# LNA.net
KiCad netlist of a schematic drawn in Altium Designer
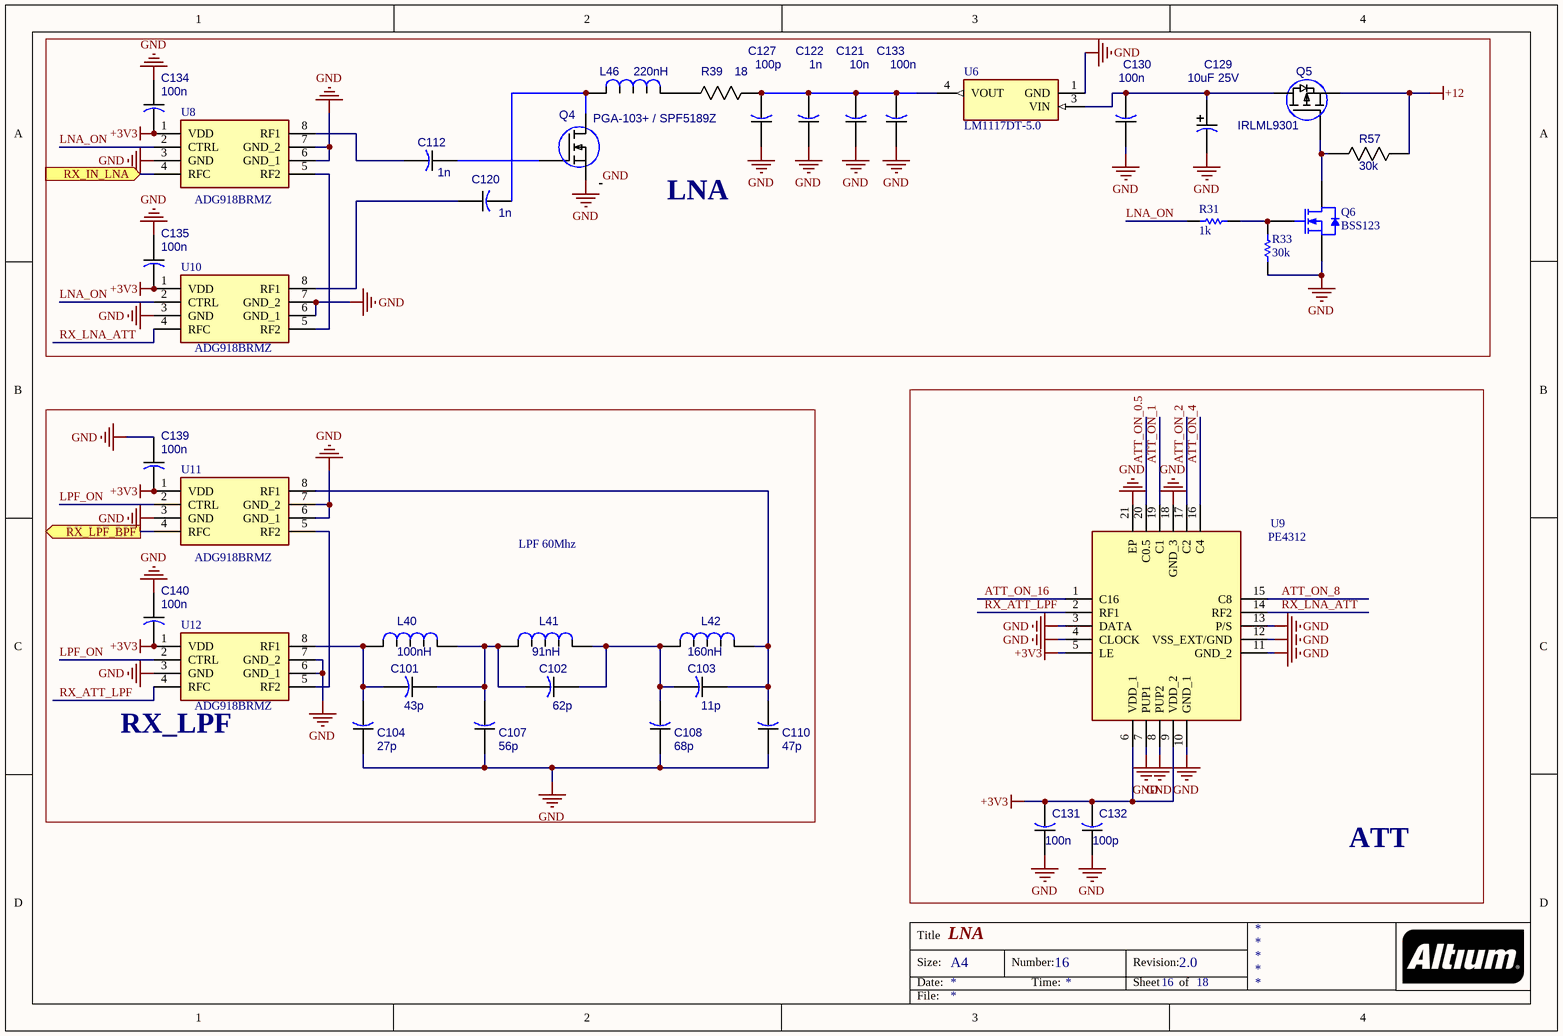
[diagram p0: LNA.SchDoc]

(export (version "E")
  (design (tool "Eeschema 10.0.6"))
  (components
    (comp (ref "C101")
      (value "43p")
      (footprint "CAP_0805")
      (description "CAP_0805")
      (libsource (lib "*") (part "CAP_0805"))
    )
    (comp (ref "C102")
      (value "62p")
      (footprint "CAP_0805")
      (description "CAP_0805")
      (libsource (lib "*") (part "CAP_0805"))
    )
    (comp (ref "C103")
      (value "11p")
      (footprint "CAP_0805")
      (description "CAP_0805")
      (libsource (lib "*") (part "CAP_0805"))
    )
    (comp (ref "C104")
      (value "27p")
      (footprint "CAP_0805")
      (description "CAP_0805")
      (libsource (lib "*") (part "CAP_0805"))
    )
    (comp (ref "C107")
      (value "56p")
      (footprint "CAP_0805")
      (description "CAP_0805")
      (libsource (lib "*") (part "CAP_0805"))
    )
    (comp (ref "C108")
      (value "68p")
      (footprint "CAP_0805")
      (description "CAP_0805")
      (libsource (lib "*") (part "CAP_0805"))
    )
    (comp (ref "C110")
      (value "47p")
      (footprint "CAP_0805")
      (description "CAP_0805")
      (libsource (lib "*") (part "CAP_0805"))
    )
    (comp (ref "C112")
      (value "1n")
      (footprint "CAP_0805")
      (description "CAP_0805")
      (libsource (lib "*") (part "CAP_0805"))
    )
    (comp (ref "C120")
      (value "1n")
      (footprint "CAP_0805")
      (description "CAP_0805")
      (libsource (lib "*") (part "CAP_0805"))
    )
    (comp (ref "C121")
      (value "10n")
      (footprint "6-0805_M")
      (description "CAP_0805")
      (libsource (lib "*") (part "CAP_0805"))
    )
    (comp (ref "C122")
      (value "1n")
      (footprint "6-0805_M")
      (description "CAP_0805")
      (libsource (lib "*") (part "CAP_0805"))
    )
    (comp (ref "C127")
      (value "100p")
      (footprint "6-0805_M")
      (description "CAP_0805")
      (libsource (lib "*") (part "CAP_0805"))
    )
    (comp (ref "C129")
      (value "10uF 25V")
      (footprint "CAPAE_5.3x5.3h6.1")
      (description "CAPAE_5.3x5.3h6.1")
      (libsource (lib "*") (part "CAPAE_5.3x5.3h6.1"))
    )
    (comp (ref "C130")
      (value "100n")
      (footprint "CAP_0805")
      (description "CAP_0805")
      (libsource (lib "") (part "CAP_0805_1"))
    )
    (comp (ref "C131")
      (value "100n")
      (footprint "6-0805_M")
      (description "CAP_0805")
      (libsource (lib "*") (part "CAP_0805"))
    )
    (comp (ref "C132")
      (value "100p")
      (footprint "6-0805_M")
      (description "CAP_0805")
      (libsource (lib "*") (part "CAP_0805"))
    )
    (comp (ref "C133")
      (value "100n")
      (footprint "CAP_0805")
      (description "CAP_0805")
      (libsource (lib "*") (part "CAP_0805"))
    )
    (comp (ref "C134")
      (value "100n")
      (footprint "CAP_0805")
      (description "CAP_0805")
      (libsource (lib "*") (part "CAP_0805"))
    )
    (comp (ref "C135")
      (value "100n")
      (footprint "CAP_0805")
      (description "CAP_0805")
      (libsource (lib "*") (part "CAP_0805"))
    )
    (comp (ref "C139")
      (value "100n")
      (footprint "CAP_0805")
      (description "CAP_0805")
      (libsource (lib "*") (part "CAP_0805"))
    )
    (comp (ref "C140")
      (value "100n")
      (footprint "CAP_0805")
      (description "CAP_0805")
      (libsource (lib "*") (part "CAP_0805"))
    )
    (comp (ref "L40")
      (value "100nH")
      (footprint "IND_0805")
      (description "IND_0805")
      (libsource (lib "*") (part "IND_0805"))
    )
    (comp (ref "L41")
      (value "91nH")
      (footprint "IND_0805")
      (description "IND_0805")
      (libsource (lib "*") (part "IND_0805"))
    )
    (comp (ref "L42")
      (value "160nH")
      (footprint "IND_0805")
      (description "IND_0805")
      (libsource (lib "*") (part "IND_0805"))
    )
    (comp (ref "L46")
      (value "220nH")
      (footprint "IND_1206")
      (description "IND_1206")
      (libsource (lib "*") (part "IND_1206"))
    )
    (comp (ref "Q4")
      (value "PGA-103+ / SPF5189Z")
      (footprint "SOT89")
      (libsource (lib "*") (part "PGA-103+"))
    )
    (comp (ref "Q5")
      (value "IRLML9301")
      (footprint "SOT23")
      (description "MOSFET")
      (libsource (lib "*") (part "MOSFET_ENH_PD"))
    )
    (comp (ref "Q6")
      (value "BSS123")
      (footprint "FAIR-SOT23-3_V")
      (fields (field (name "MANUFACTURER") "Fairchild"))
      (libsource (lib "Altium Content Vault") (part "NEMOS-GSD-3"))
    )
    (comp (ref "R31")
      (value "1k")
      (footprint "RESC2013X60X40NL20T25")
      (description "RES_0805")
      (fields (field (name "MANUFACTURER") "Panasonic") (field (name "PART NUMBER") "ERA-6AEB303V"))
      (libsource (lib "Altium Content Vault") (part "RES"))
    )
    (comp (ref "R33")
      (value "30k")
      (footprint "RESC2013X60X40NL20T25")
      (description "RES_0805")
      (fields (field (name "MANUFACTURER") "Panasonic") (field (name "PART NUMBER") "ERA-6AEB303V"))
      (libsource (lib "Altium Content Vault") (part "RES"))
    )
    (comp (ref "R39")
      (value "18")
      (footprint "RES_1206")
      (description "RES_1206")
      (libsource (lib "*") (part "RES_1206"))
    )
    (comp (ref "R57")
      (value "30k")
      (footprint "RES_0805")
      (description "RES_0805")
      (libsource (lib "*") (part "RES_0805"))
    )
    (comp (ref "U6")
      (value "LM1117DT-5.0")
      (footprint "SamacSys:TO228P991X238-3N")
      (description "Integrated Circuit")
      (fields
        (field (name "MANUFACTURER_PART_NUMBER") "LM1117DT-ADJ")
        (field (name "MOUSER PART NUMBER") "926-LM1117DT-ADJ")
      )
      (libsource (lib "*") (part "LM1117DT-ADJ"))
    )
    (comp (ref "U8")
      (value "ADG918BRMZ")
      (footprint "SamacSys:SOP65P490X110-8N")
      (description "Integrated Circuit")
      (fields (field (name "MOUSER PART NUMBER") "584-ADG918BRMZ") (field (name "RS PART NUMBER") "4969212P"))
      (libsource (lib "*") (part "ADG918BRMZ"))
    )
    (comp (ref "U9")
      (value "PE4312")
      (footprint "SamacSys:QFN50P400X400X90-21N")
      (description "Integrated Circuit")
      (fields (field (name "MANUFACTURER_PART_NUMBER") "PE4312C-Z"))
      (libsource (lib "*") (part "PE4312C-Z"))
    )
    (comp (ref "U10")
      (value "ADG918BRMZ")
      (footprint "SamacSys:SOP65P490X110-8N")
      (description "Integrated Circuit")
      (fields (field (name "MOUSER PART NUMBER") "584-ADG918BRMZ") (field (name "RS PART NUMBER") "4969212P"))
      (libsource (lib "*") (part "ADG918BRMZ"))
    )
    (comp (ref "U11")
      (value "ADG918BRMZ")
      (footprint "SamacSys:SOP65P490X110-8N")
      (description "Integrated Circuit")
      (fields (field (name "MOUSER PART NUMBER") "584-ADG918BRMZ") (field (name "RS PART NUMBER") "4969212P"))
      (libsource (lib "*") (part "ADG918BRMZ"))
    )
    (comp (ref "U12")
      (value "ADG918BRMZ")
      (footprint "SamacSys:SOP65P490X110-8N")
      (description "Integrated Circuit")
      (fields (field (name "MOUSER PART NUMBER") "584-ADG918BRMZ") (field (name "RS PART NUMBER") "4969212P"))
      (libsource (lib "*") (part "ADG918BRMZ"))
    )
  )
  (nets
    (net (code "1") (name "+3V3") (class "Default")
      (node (ref "C131") (pin "2") (pinfunction "2_2") (pintype "passive"))
      (node (ref "C132") (pin "2") (pinfunction "2_2") (pintype "passive"))
      (node (ref "C134") (pin "2") (pinfunction "2_2") (pintype "passive"))
      (node (ref "C135") (pin "2") (pinfunction "2_2") (pintype "passive"))
      (node (ref "C139") (pin "2") (pinfunction "2_2") (pintype "passive"))
      (node (ref "C140") (pin "2") (pinfunction "2_2") (pintype "passive"))
      (node (ref "U10") (pin "1") (pinfunction "VDD_1") (pintype "power_in"))
      (node (ref "U11") (pin "1") (pinfunction "VDD_1") (pintype "power_in"))
      (node (ref "U12") (pin "1") (pinfunction "VDD_1") (pintype "power_in"))
      (node (ref "U8") (pin "1") (pinfunction "VDD_1") (pintype "power_in"))
      (node (ref "U9") (pin "5") (pinfunction "LE_5") (pintype "passive"))
      (node (ref "U9") (pin "6") (pinfunction "VDD_1_6") (pintype "passive"))
      (node (ref "U9") (pin "9") (pinfunction "VDD_2_9") (pintype "passive"))
    )
    (net (code "2") (name "+12") (class "Default")
      (node (ref "Q5") (pin "2") (pinfunction "S_2") (pintype "passive"))
      (node (ref "R57") (pin "2") (pinfunction "2_2") (pintype "passive"))
    )
    (net (code "3") (name "/ATT_ON_0.5") (class "Default")
      (node (ref "U9") (pin "20") (pinfunction "C0.5_20") (pintype "passive"))
    )
    (net (code "4") (name "/ATT_ON_1") (class "Default")
      (node (ref "U9") (pin "19") (pinfunction "C1_19") (pintype "passive"))
    )
    (net (code "5") (name "/ATT_ON_2") (class "Default")
      (node (ref "U9") (pin "17") (pinfunction "C2_17") (pintype "passive"))
    )
    (net (code "6") (name "/ATT_ON_4") (class "Default")
      (node (ref "U9") (pin "16") (pinfunction "C4_16") (pintype "passive"))
    )
    (net (code "7") (name "/ATT_ON_8") (class "Default")
      (node (ref "U9") (pin "15") (pinfunction "C8_15") (pintype "passive"))
    )
    (net (code "8") (name "/ATT_ON_16") (class "Default")
      (node (ref "U9") (pin "1") (pinfunction "C16_1") (pintype "passive"))
    )
    (net (code "9") (name "/LNA_ON") (class "Default")
      (node (ref "R31") (pin "2") (pinfunction "2_2") (pintype "passive"))
      (node (ref "U10") (pin "2") (pinfunction "CTRL_2") (pintype "passive"))
      (node (ref "U8") (pin "2") (pinfunction "CTRL_2") (pintype "passive"))
    )
    (net (code "10") (name "/LPF_ON") (class "Default")
      (node (ref "U11") (pin "2") (pinfunction "CTRL_2") (pintype "passive"))
      (node (ref "U12") (pin "2") (pinfunction "CTRL_2") (pintype "passive"))
    )
    (net (code "11") (name "/RX_ATT_LPF") (class "Default")
      (node (ref "U12") (pin "4") (pinfunction "RFC_4") (pintype "passive"))
      (node (ref "U9") (pin "2") (pinfunction "RF1_2") (pintype "passive"))
    )
    (net (code "12") (name "/RX_IN_LNA") (class "Default")
      (node (ref "U8") (pin "4") (pinfunction "RFC_4") (pintype "passive"))
    )
    (net (code "13") (name "/RX_LNA_ATT") (class "Default")
      (node (ref "U10") (pin "4") (pinfunction "RFC_4") (pintype "passive"))
      (node (ref "U9") (pin "14") (pinfunction "RF2_14") (pintype "passive"))
    )
    (net (code "14") (name "/RX_LPF_BPF") (class "Default")
      (node (ref "U11") (pin "4") (pinfunction "RFC_4") (pintype "passive"))
    )
    (net (code "15") (name "GND") (class "Default")
      (node (ref "C104") (pin "1") (pinfunction "1_1") (pintype "passive"))
      (node (ref "C107") (pin "1") (pinfunction "1_1") (pintype "passive"))
      (node (ref "C108") (pin "1") (pinfunction "1_1") (pintype "passive"))
      (node (ref "C110") (pin "1") (pinfunction "1_1") (pintype "passive"))
      (node (ref "C121") (pin "1") (pinfunction "1_1") (pintype "passive"))
      (node (ref "C122") (pin "1") (pinfunction "1_1") (pintype "passive"))
      (node (ref "C127") (pin "1") (pinfunction "1_1") (pintype "passive"))
      (node (ref "C129") (pin "2") (pinfunction "MINUS_2") (pintype "passive"))
      (node (ref "C130") (pin "1") (pinfunction "1_1") (pintype "passive"))
      (node (ref "C131") (pin "1") (pinfunction "1_1") (pintype "passive"))
      (node (ref "C132") (pin "1") (pinfunction "1_1") (pintype "passive"))
      (node (ref "C133") (pin "1") (pinfunction "1_1") (pintype "passive"))
      (node (ref "C134") (pin "1") (pinfunction "1_1") (pintype "passive"))
      (node (ref "C135") (pin "1") (pinfunction "1_1") (pintype "passive"))
      (node (ref "C139") (pin "1") (pinfunction "1_1") (pintype "passive"))
      (node (ref "C140") (pin "1") (pinfunction "1_1") (pintype "passive"))
      (node (ref "Q4") (pin "0") (pinfunction "0_0") (pintype "passive"))
      (node (ref "Q4") (pin "2") (pinfunction "S_2") (pintype "passive"))
      (node (ref "Q6") (pin "2") (pinfunction "S_2") (pintype "passive"))
      (node (ref "R33") (pin "1") (pinfunction "1_1") (pintype "passive"))
      (node (ref "U10") (pin "3") (pinfunction "GND_3") (pintype "power_in"))
      (node (ref "U10") (pin "6") (pinfunction "GND_1_6") (pintype "power_in"))
      (node (ref "U10") (pin "7") (pinfunction "GND_2_7") (pintype "power_in"))
      (node (ref "U11") (pin "3") (pinfunction "GND_3") (pintype "power_in"))
      (node (ref "U11") (pin "6") (pinfunction "GND_1_6") (pintype "power_in"))
      (node (ref "U11") (pin "7") (pinfunction "GND_2_7") (pintype "power_in"))
      (node (ref "U12") (pin "3") (pinfunction "GND_3") (pintype "power_in"))
      (node (ref "U12") (pin "6") (pinfunction "GND_1_6") (pintype "power_in"))
      (node (ref "U12") (pin "7") (pinfunction "GND_2_7") (pintype "power_in"))
      (node (ref "U6") (pin "1") (pinfunction "GND_1") (pintype "passive"))
      (node (ref "U8") (pin "3") (pinfunction "GND_3") (pintype "power_in"))
      (node (ref "U8") (pin "6") (pinfunction "GND_1_6") (pintype "power_in"))
      (node (ref "U8") (pin "7") (pinfunction "GND_2_7") (pintype "power_in"))
      (node (ref "U9") (pin "10") (pinfunction "GND_1_10") (pintype "passive"))
      (node (ref "U9") (pin "11") (pinfunction "GND_2_11") (pintype "passive"))
      (node (ref "U9") (pin "12") (pinfunction "VSS_EXT/GND_12") (pintype "passive"))
      (node (ref "U9") (pin "13") (pinfunction "P/S_13") (pintype "passive"))
      (node (ref "U9") (pin "18") (pinfunction "GND_3_18") (pintype "passive"))
      (node (ref "U9") (pin "21") (pinfunction "EP_21") (pintype "passive"))
      (node (ref "U9") (pin "3") (pinfunction "DATA_3") (pintype "passive"))
      (node (ref "U9") (pin "4") (pinfunction "CLOCK_4") (pintype "passive"))
      (node (ref "U9") (pin "7") (pinfunction "PUP1_7") (pintype "passive"))
      (node (ref "U9") (pin "8") (pinfunction "PUP2_8") (pintype "passive"))
    )
    (net (code "16") (name "Net-(C101-Pad1)") (class "Default")
      (node (ref "C101") (pin "1") (pinfunction "1_1") (pintype "passive"))
      (node (ref "C102") (pin "2") (pinfunction "2_2") (pintype "passive"))
      (node (ref "C107") (pin "2") (pinfunction "2_2") (pintype "passive"))
      (node (ref "L40") (pin "2") (pinfunction "2_2") (pintype "passive"))
      (node (ref "L41") (pin "1") (pinfunction "1_1") (pintype "passive"))
    )
    (net (code "17") (name "Net-(C102-Pad1)") (class "Default")
      (node (ref "C102") (pin "1") (pinfunction "1_1") (pintype "passive"))
      (node (ref "C103") (pin "2") (pinfunction "2_2") (pintype "passive"))
      (node (ref "C108") (pin "2") (pinfunction "2_2") (pintype "passive"))
      (node (ref "L41") (pin "2") (pinfunction "2_2") (pintype "passive"))
      (node (ref "L42") (pin "1") (pinfunction "1_1") (pintype "passive"))
    )
    (net (code "18") (name "Net-(C129-PLUS)") (class "Default")
      (node (ref "C129") (pin "1") (pinfunction "PLUS_1") (pintype "passive"))
      (node (ref "C130") (pin "2") (pinfunction "2_2") (pintype "passive"))
      (node (ref "Q5") (pin "3") (pinfunction "D_3") (pintype "passive"))
      (node (ref "U6") (pin "3") (pinfunction "VIN_3") (pintype "input"))
    )
    (net (code "19") (name "Net-(L46-1)") (class "Default")
      (node (ref "C120") (pin "2") (pinfunction "2_2") (pintype "passive"))
      (node (ref "L46") (pin "2") (pinfunction "1_2") (pintype "passive"))
      (node (ref "Q4") (pin "3") (pinfunction "D_3") (pintype "passive"))
    )
    (net (code "20") (name "Net-(L46-2)") (class "Default")
      (node (ref "L46") (pin "1") (pinfunction "2_1") (pintype "passive"))
      (node (ref "R39") (pin "2") (pinfunction "2_2") (pintype "passive"))
    )
    (net (code "21") (name "Net-(Q4-G)") (class "Default")
      (node (ref "C112") (pin "1") (pinfunction "1_1") (pintype "passive"))
      (node (ref "Q4") (pin "1") (pinfunction "G_1") (pintype "passive"))
    )
    (net (code "22") (name "Net-(Q5-G)") (class "Default")
      (node (ref "Q5") (pin "1") (pinfunction "G_1") (pintype "passive"))
      (node (ref "Q6") (pin "3") (pinfunction "D_3") (pintype "passive"))
      (node (ref "R57") (pin "1") (pinfunction "1_1") (pintype "passive"))
    )
    (net (code "23") (name "Net-(Q6-G)") (class "Default")
      (node (ref "Q6") (pin "1") (pinfunction "G_1") (pintype "passive"))
      (node (ref "R31") (pin "1") (pinfunction "1_1") (pintype "passive"))
      (node (ref "R33") (pin "2") (pinfunction "2_2") (pintype "passive"))
    )
    (net (code "24") (name "Net-(U6-VOUT)") (class "Default")
      (node (ref "C121") (pin "2") (pinfunction "2_2") (pintype "passive"))
      (node (ref "C122") (pin "2") (pinfunction "2_2") (pintype "passive"))
      (node (ref "C127") (pin "2") (pinfunction "2_2") (pintype "passive"))
      (node (ref "C133") (pin "2") (pinfunction "2_2") (pintype "passive"))
      (node (ref "R39") (pin "1") (pinfunction "1_1") (pintype "passive"))
      (node (ref "U6") (pin "4") (pinfunction "VOUT_4") (pintype "output"))
    )
    (net (code "25") (name "Net-(U8-RF1)") (class "Default")
      (node (ref "C112") (pin "2") (pinfunction "2_2") (pintype "passive"))
      (node (ref "U8") (pin "8") (pinfunction "RF1_8") (pintype "passive"))
    )
    (net (code "26") (name "Net-(U10-RF1)") (class "Default")
      (node (ref "C120") (pin "1") (pinfunction "1_1") (pintype "passive"))
      (node (ref "U10") (pin "8") (pinfunction "RF1_8") (pintype "passive"))
    )
    (net (code "27") (name "Net-(U10-RF2)") (class "Default")
      (node (ref "U10") (pin "5") (pinfunction "RF2_5") (pintype "passive"))
      (node (ref "U8") (pin "5") (pinfunction "RF2_5") (pintype "passive"))
    )
    (net (code "28") (name "Net-(U11-RF1)") (class "Default")
      (node (ref "C103") (pin "1") (pinfunction "1_1") (pintype "passive"))
      (node (ref "C110") (pin "2") (pinfunction "2_2") (pintype "passive"))
      (node (ref "L42") (pin "2") (pinfunction "2_2") (pintype "passive"))
      (node (ref "U11") (pin "8") (pinfunction "RF1_8") (pintype "passive"))
    )
    (net (code "29") (name "Net-(U11-RF2)") (class "Default")
      (node (ref "U11") (pin "5") (pinfunction "RF2_5") (pintype "passive"))
      (node (ref "U12") (pin "5") (pinfunction "RF2_5") (pintype "passive"))
    )
    (net (code "30") (name "Net-(U12-RF1)") (class "Default")
      (node (ref "C101") (pin "2") (pinfunction "2_2") (pintype "passive"))
      (node (ref "C104") (pin "2") (pinfunction "2_2") (pintype "passive"))
      (node (ref "L40") (pin "1") (pinfunction "1_1") (pintype "passive"))
      (node (ref "U12") (pin "8") (pinfunction "RF1_8") (pintype "passive"))
    )
  )
)
